# GPS.net
KiCad netlist of a schematic drawn in Altium Designer
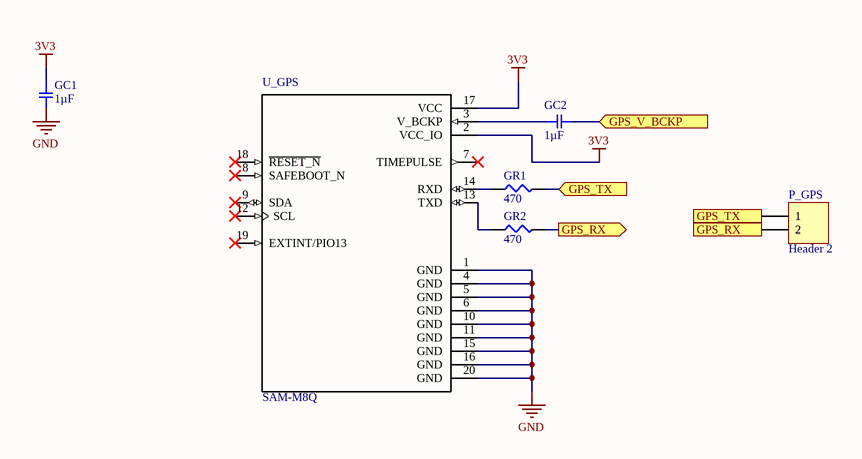
[diagram p0: GPS.SchDoc]

(export (version "E")
  (design (tool "Eeschema 10.0.6"))
  (components
    (comp (ref "GC1")
      (value "1µF")
      (footprint "SMD-0603C")
      (description "CAP CER 1UF 10V X5R 0603")
      (fields
        (field (name "DIGI-KEY PART NUMBER") "490-1543-1-ND")
        (field (name "PART NUMBER") "GRM188R61A105KA61D")
      )
      (libsource (lib "capacitor_murata_0603") (part "GRM188R61A105KA61D"))
    )
    (comp (ref "GC2")
      (value "1µF")
      (footprint "SMD-0603C")
      (description "CAP CER 1UF 10V X5R 0603")
      (fields
        (field (name "DIGI-KEY PART NUMBER") "490-1543-1-ND")
        (field (name "PART NUMBER") "GRM188R61A105KA61D")
      )
      (libsource (lib "capacitor_murata_0603") (part "GRM188R61A105KA61D"))
    )
    (comp (ref "GR1")
      (value "470")
      (footprint "SMD-0603-RES")
      (description "RES SMD 470 OHM 1% 1/10W 0603")
      (fields (field (name "PART NUMBER") "ERJ-3EKF4700V") (field (name "DIGI-KEY PART NUMBER") "P470HCT-ND"))
      (libsource (lib "Panasonic_ERJ_0603") (part "ERJ-3EKF4700V"))
    )
    (comp (ref "GR2")
      (value "470")
      (footprint "SMD-0603-RES")
      (description "RES SMD 470 OHM 1% 1/10W 0603")
      (fields (field (name "PART NUMBER") "ERJ-3EKF4700V") (field (name "DIGI-KEY PART NUMBER") "P470HCT-ND"))
      (libsource (lib "Panasonic_ERJ_0603") (part "ERJ-3EKF4700V"))
    )
    (comp (ref "P_GPS")
      (value "Header 2")
      (footprint "HDR1X2")
      (description "Header, 2-Pin")
      (fields (field (name "PUBLISHER") "Altium Limited"))
      (libsource (lib "Miscellaneous Connectors") (part "Header 2"))
    )
    (comp (ref "U_GPS")
      (value "SAM-M8Q")
      (footprint "*XCVR_SAM-M8Q")
      (description "u-Blox M8 Gnss Antenna Module")
      (fields (field (name "MF") "U-Blox America") (field (name "DIGI-KEY_PART_NUMBER") "672-1054-1-ND"))
      (libsource (lib "SAM-M8Q") (part "SAM-M8Q"))
    )
  )
  (nets
    (net (code "1") (name "/GPS_RX") (class "Default")
      (node (ref "GR2") (pin "2") (pinfunction "2_2") (pintype "passive"))
      (node (ref "P_GPS") (pin "2") (pinfunction "2_2") (pintype "passive"))
    )
    (net (code "2") (name "/GPS_TX") (class "Default")
      (node (ref "GR1") (pin "2") (pinfunction "2_2") (pintype "passive"))
      (node (ref "P_GPS") (pin "1") (pinfunction "1_1") (pintype "passive"))
    )
    (net (code "3") (name "/GPS_V_BCKP") (class "Default")
      (node (ref "GC2") (pin "2") (pinfunction "2_2") (pintype "passive"))
    )
    (net (code "4") (name "3V3") (class "Default")
      (node (ref "GC1") (pin "1") (pinfunction "1_1") (pintype "passive"))
      (node (ref "U_GPS") (pin "17") (pinfunction "VCC_17") (pintype "power_in"))
      (node (ref "U_GPS") (pin "2") (pinfunction "VCC_IO_2") (pintype "power_in"))
    )
    (net (code "5") (name "GND") (class "Default")
      (node (ref "GC1") (pin "2") (pinfunction "2_2") (pintype "passive"))
      (node (ref "U_GPS") (pin "1") (pinfunction "GND_1") (pintype "power_in"))
      (node (ref "U_GPS") (pin "10") (pinfunction "GND_10") (pintype "power_in"))
      (node (ref "U_GPS") (pin "11") (pinfunction "GND_11") (pintype "power_in"))
      (node (ref "U_GPS") (pin "15") (pinfunction "GND_15") (pintype "power_in"))
      (node (ref "U_GPS") (pin "16") (pinfunction "GND_16") (pintype "power_in"))
      (node (ref "U_GPS") (pin "20") (pinfunction "GND_20") (pintype "power_in"))
      (node (ref "U_GPS") (pin "4") (pinfunction "GND_4") (pintype "power_in"))
      (node (ref "U_GPS") (pin "5") (pinfunction "GND_5") (pintype "power_in"))
      (node (ref "U_GPS") (pin "6") (pinfunction "GND_6") (pintype "power_in"))
    )
    (net (code "6") (name "Net-(U_GPS-RXD)") (class "Default")
      (node (ref "GR1") (pin "1") (pinfunction "1_1") (pintype "passive"))
      (node (ref "U_GPS") (pin "14") (pinfunction "RXD_14") (pintype "bidirectional"))
    )
    (net (code "7") (name "Net-(U_GPS-TXD)") (class "Default")
      (node (ref "GR2") (pin "1") (pinfunction "1_1") (pintype "passive"))
      (node (ref "U_GPS") (pin "13") (pinfunction "TXD_13") (pintype "bidirectional"))
    )
    (net (code "8") (name "Net-(U_GPS-V_BCKP)") (class "Default")
      (node (ref "GC2") (pin "1") (pinfunction "1_1") (pintype "passive"))
      (node (ref "U_GPS") (pin "3") (pinfunction "V_BCKP_3") (pintype "input"))
    )
    (net (code "9") (name "unconnected-(U_GPS-EXTINT{slash}PIO13-Pad19)") (class "Default")
      (node (ref "U_GPS") (pin "19") (pinfunction "EXTINT/PIO13_19") (pintype "input+no_connect"))
    )
    (net (code "10") (name "unconnected-(U_GPS-SAFEBOOT_N-Pad8)") (class "Default")
      (node (ref "U_GPS") (pin "8") (pinfunction "SAFEBOOT_N_8") (pintype "input+no_connect"))
    )
    (net (code "11") (name "unconnected-(U_GPS-SCL-Pad12)") (class "Default")
      (node (ref "U_GPS") (pin "12") (pinfunction "SCL_12") (pintype "input+no_connect"))
    )
    (net (code "12") (name "unconnected-(U_GPS-SDA-Pad9)") (class "Default")
      (node (ref "U_GPS") (pin "9") (pinfunction "SDA_9") (pintype "bidirectional+no_connect"))
    )
    (net (code "13") (name "unconnected-(U_GPS-TIMEPULSE-Pad7)") (class "Default")
      (node (ref "U_GPS") (pin "7") (pinfunction "TIMEPULSE_7") (pintype "output+no_connect"))
    )
    (net (code "14") (name "unconnected-(U_GPS-~{RESET_N}-Pad18)") (class "Default")
      (node (ref "U_GPS") (pin "18") (pinfunction "~{RESET_N}_18") (pintype "input+no_connect"))
    )
  )
)
